# Sheet1_v3.net
KiCad netlist of a schematic drawn in Altium Designer
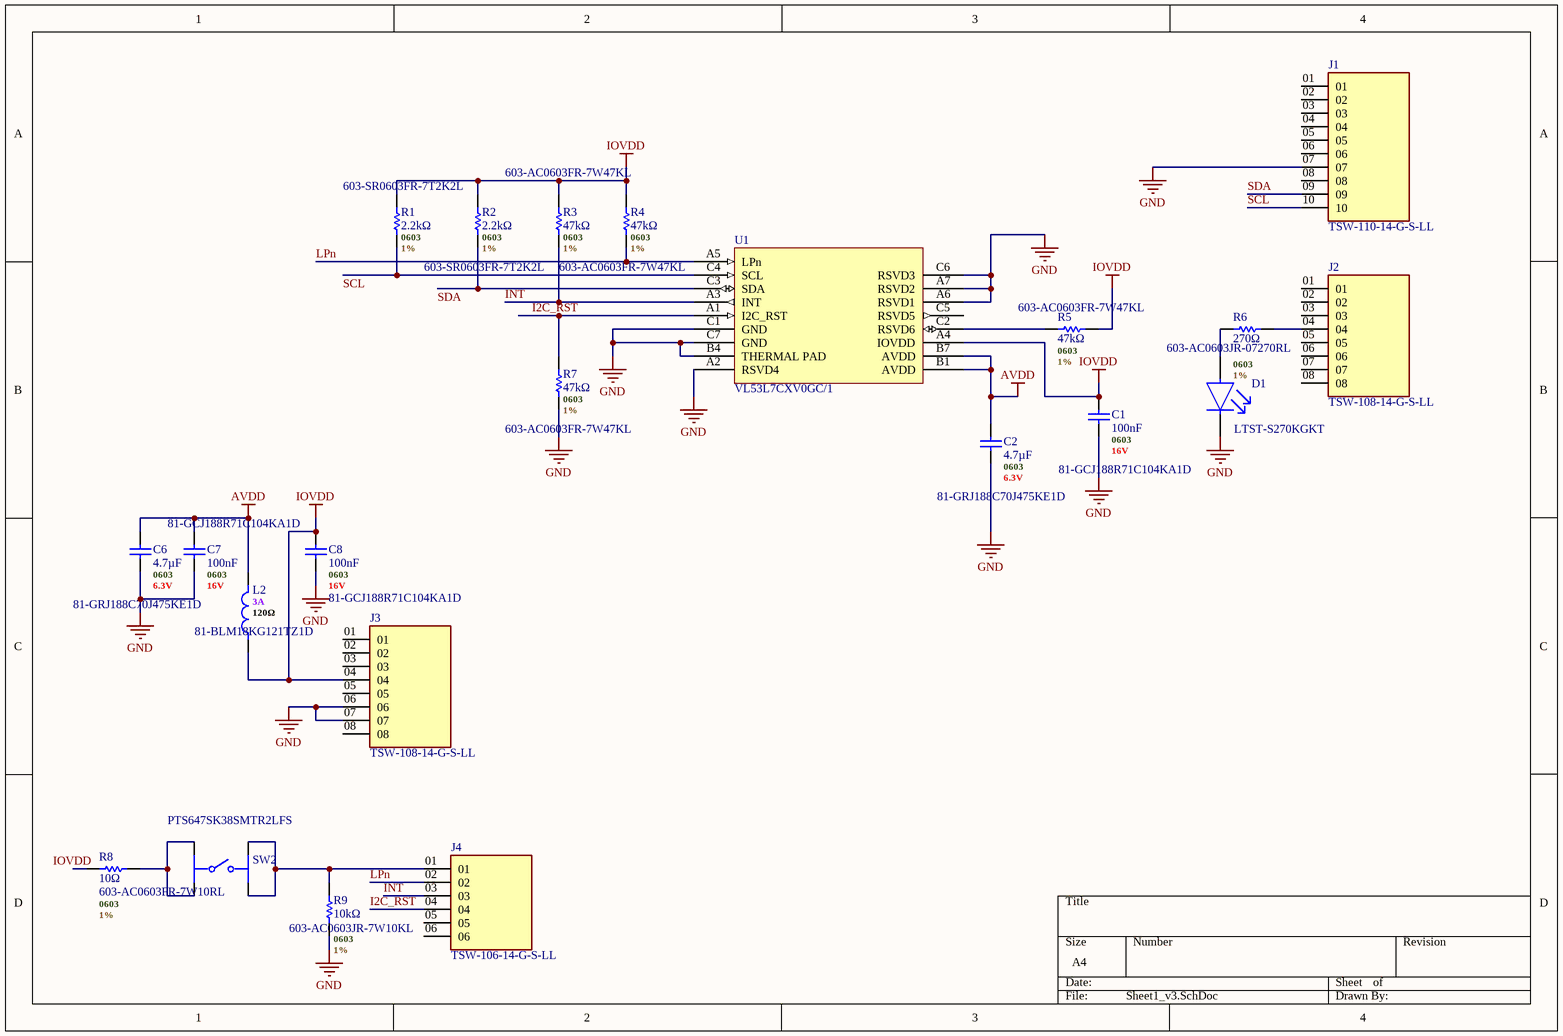
[diagram p0: Sheet1_v3.SchDoc]

(export (version "E")
  (design (tool "Eeschema 10.0.6"))
  (components
    (comp (ref "C1")
      (value "100nF")
      (footprint "C0603 - MURATA")
      (description "Ceramic Capacitor, Ceramic, 16V, 10% +Tol, 10% -Tol, X7R, 15% TC, 0.1uF, Surface Mount, 0603")
      (fields
        (field (name "MANUFACTURER") "Murata")
        (field (name "MANUFACTURER PART NUMBER") "GCJ188R71C104KA01D")
        (field (name ".CASE/PACKAGE") "0603")
        (field (name ".VOLTAGE RATING (DC)") "16V")
        (field (name "SUPPLIER PART NUMBER 1") "81-GCJ188R71C104KA1D")
      )
      (libsource (lib "CAP_GCJ188R71C104KA01D") (part "CAP - GENERIC"))
    )
    (comp (ref "C2")
      (value "4.7µF")
      (footprint "C0603 - MURATA")
      (description "GRJ Series 0603 6.3 V 4.7 uF ±10% X7S SMT Multilayer Ceramic Capacitor")
      (fields
        (field (name "MANUFACTURER") "Murata")
        (field (name "MANUFACTURER PART NUMBER") "GRJ188C70J475KE11D")
        (field (name ".CASE/PACKAGE") "0603")
        (field (name ".VOLTAGE RATING (DC)") "6.3V")
        (field (name "SUPPLIER PART NUMBER 1") "81-GRJ188C70J475KE1D")
      )
      (libsource (lib "CAP_GRJ188C70J475KE11D") (part "CAP - GENERIC"))
    )
    (comp (ref "C6")
      (value "4.7µF")
      (footprint "C0603 - MURATA")
      (description "GRJ Series 0603 6.3 V 4.7 uF ±10% X7S SMT Multilayer Ceramic Capacitor")
      (fields
        (field (name "MANUFACTURER") "Murata")
        (field (name "MANUFACTURER PART NUMBER") "GRJ188C70J475KE11D")
        (field (name ".CASE/PACKAGE") "0603")
        (field (name ".VOLTAGE RATING (DC)") "6.3V")
        (field (name "SUPPLIER PART NUMBER 1") "81-GRJ188C70J475KE1D")
      )
      (libsource (lib "CAP_GRJ188C70J475KE11D") (part "CAP - GENERIC"))
    )
    (comp (ref "C7")
      (value "100nF")
      (footprint "C0603 - MURATA")
      (description "Ceramic Capacitor, Ceramic, 16V, 10% +Tol, 10% -Tol, X7R, 15% TC, 0.1uF, Surface Mount, 0603")
      (fields
        (field (name "MANUFACTURER") "Murata")
        (field (name "MANUFACTURER PART NUMBER") "GCJ188R71C104KA01D")
        (field (name ".CASE/PACKAGE") "0603")
        (field (name ".VOLTAGE RATING (DC)") "16V")
        (field (name "SUPPLIER PART NUMBER 1") "81-GCJ188R71C104KA1D")
      )
      (libsource (lib "CAP_GCJ188R71C104KA01D") (part "CAP - GENERIC"))
    )
    (comp (ref "C8")
      (value "100nF")
      (footprint "C0603 - MURATA")
      (description "Ceramic Capacitor, Ceramic, 16V, 10% +Tol, 10% -Tol, X7R, 15% TC, 0.1uF, Surface Mount, 0603")
      (fields
        (field (name "MANUFACTURER") "Murata")
        (field (name "MANUFACTURER PART NUMBER") "GCJ188R71C104KA01D")
        (field (name ".CASE/PACKAGE") "0603")
        (field (name ".VOLTAGE RATING (DC)") "16V")
        (field (name "SUPPLIER PART NUMBER 1") "81-GCJ188R71C104KA1D")
      )
      (libsource (lib "CAP_GCJ188R71C104KA01D") (part "CAP - GENERIC"))
    )
    (comp (ref "D1")
      (value "LTST-S270KGKT")
      (footprint "FP-LTST-S270KGKT-MFG")
      (description "LED GREEN CLEAR CHIP SMD R/A")
      (libsource (lib "Altium Content Vault") (part "8706943c75ba83719d021d2fdc84c58"))
    )
    (comp (ref "J1")
      (value "TSW-110-14-G-S-LL")
      (footprint "SAMTEC_TSW-110-14-G-S-LL")
      (libsource (lib "TSW-110-14-G-S-LL") (part "TSW-110-14-G-S-LL"))
    )
    (comp (ref "J2")
      (value "TSW-108-14-G-S-LL")
      (footprint "SAMTEC_TSW-108-14-G-S-LL")
      (libsource (lib "TSW-108-14-G-S-LL") (part "TSW-108-14-G-S-LL"))
    )
    (comp (ref "J3")
      (value "TSW-108-14-G-S-LL")
      (footprint "SAMTEC_TSW-108-14-G-S-LL")
      (libsource (lib "TSW-108-14-G-S-LL") (part "TSW-108-14-G-S-LL"))
    )
    (comp (ref "J4")
      (value "TSW-106-14-G-S-LL")
      (footprint "SAMTEC_TSW-106-14-G-S-LL")
      (libsource (lib "TSW-106-14-G-S-LL") (part "TSW-106-14-G-S-LL"))
    )
    (comp (ref "L2")
      (value "BLM18KG121TZ1D")
      (footprint "BLM18KG121TZ1D")
      (description "Ferrite Beads Multi-Layer Power 120Ohm 25% 100MHz 3A 0.03Ohm DCR 0603 T/R Automotive AEC-Q200")
      (fields
        (field (name "MANUFACTURER") "Murata")
        (field (name "TOLERANCE") "25%")
        (field (name ".RMS CURRENT (IRMS)") "3A")
        (field (name ".VALUE") "120Ω")
        (field (name "SUPPLIER PART NUMBER 1") "81-BLM18KG121TZ1D")
      )
      (libsource (lib "INDUCTOR_BLM18KG121TZ1D") (part "INDUCTOR_BLM18KG121TZ1D"))
    )
    (comp (ref "R1")
      (value "2.2kΩ")
      (footprint "R0603 - YAGEO")
      (description "Surge Chip Resistor Automotive Grade Thick Film 0603 2.2kOhm 1% Paper T/R")
      (fields
        (field (name "MANUFACTURER") "Yageo Group")
        (field (name "MANUFACTURER PART NUMBER") "SR0603FR-7T2K2L")
        (field (name ".CASE/PACKAGE") "0603")
        (field (name ".TOLERANCE") "1%")
        (field (name "SUPPLIER PART NUMBER 1") "603-SR0603FR-7T2K2L")
      )
      (libsource (lib "RESISTOR - GENERIC") (part "RESISTOR - GENERIC"))
    )
    (comp (ref "R2")
      (value "2.2kΩ")
      (footprint "R0603 - YAGEO")
      (description "Surge Chip Resistor Automotive Grade Thick Film 0603 2.2kOhm 1% Paper T/R")
      (fields
        (field (name "MANUFACTURER") "Yageo Group")
        (field (name "MANUFACTURER PART NUMBER") "SR0603FR-7T2K2L")
        (field (name ".CASE/PACKAGE") "0603")
        (field (name ".TOLERANCE") "1%")
        (field (name "SUPPLIER PART NUMBER 1") "603-SR0603FR-7T2K2L")
      )
      (libsource (lib "RESISTOR - GENERIC") (part "RESISTOR - GENERIC"))
    )
    (comp (ref "R3")
      (value "47kΩ")
      (footprint "R0603 - YAGEO")
      (fields
        (field (name "MANUFACTURER") "Yageo Group")
        (field (name "MANUFACTURER PART NUMBER") "AC0603FR-7W47KL")
        (field (name "TOLERANCE") "1%")
        (field (name ".CASE/PACKAGE") "0603")
        (field (name ".TOLERANCE") "1%")
        (field (name "SUPPLIER PART NUMBER 1") "603-AC0603FR-7W47KL")
      )
      (libsource (lib "RESISTOR_AC0603FR-7W47KLSchLib") (part "RESISTOR - GENERIC"))
    )
    (comp (ref "R4")
      (value "47kΩ")
      (footprint "R0603 - YAGEO")
      (fields
        (field (name "MANUFACTURER") "Yageo Group")
        (field (name "MANUFACTURER PART NUMBER") "AC0603FR-7W47KL")
        (field (name "TOLERANCE") "1%")
        (field (name ".CASE/PACKAGE") "0603")
        (field (name ".TOLERANCE") "1%")
        (field (name "SUPPLIER PART NUMBER 1") "603-AC0603FR-7W47KL")
      )
      (libsource (lib "RESISTOR_AC0603FR-7W47KLSchLib") (part "RESISTOR - GENERIC"))
    )
    (comp (ref "R5")
      (value "47kΩ")
      (footprint "R0603 - YAGEO")
      (fields
        (field (name "MANUFACTURER") "Yageo Group")
        (field (name "MANUFACTURER PART NUMBER") "AC0603FR-7W47KL")
        (field (name "TOLERANCE") "1%")
        (field (name ".CASE/PACKAGE") "0603")
        (field (name ".TOLERANCE") "1%")
        (field (name "SUPPLIER PART NUMBER 1") "603-AC0603FR-7W47KL")
      )
      (libsource (lib "RESISTOR_AC0603FR-7W47KLSchLib") (part "RESISTOR - GENERIC"))
    )
    (comp (ref "R6")
      (value "270Ω")
      (footprint "R0603 - YAGEO")
      (description "Res Thick Film 0603 270 Ohm 5% 0.1W(1/10W) ±100ppm/C Pad SMD Automotive T/R")
      (fields
        (field (name "MANUFACTURER") "Yageo Group")
        (field (name "TOLERANCE") "1%")
        (field (name "SUPPLIER PART NUMBER") "603-AC0603JR-07270RL")
        (field (name ".CASE/PACKAGE") "0603")
        (field (name ".TOLERANCE") "1%")
      )
      (libsource (lib "RESISTOR_AC0603JR-07270RL") (part "RESISTOR - GENERIC"))
    )
    (comp (ref "R7")
      (value "47kΩ")
      (footprint "R0603 - YAGEO")
      (fields
        (field (name "MANUFACTURER") "Yageo Group")
        (field (name "MANUFACTURER PART NUMBER") "AC0603FR-7W47KL")
        (field (name "TOLERANCE") "1%")
        (field (name ".CASE/PACKAGE") "0603")
        (field (name ".TOLERANCE") "1%")
        (field (name "SUPPLIER PART NUMBER 1") "603-AC0603FR-7W47KL")
      )
      (libsource (lib "RESISTOR_AC0603FR-7W47KLSchLib") (part "RESISTOR - GENERIC"))
    )
    (comp (ref "R8")
      (value "10Ω")
      (footprint "R0603 - YAGEO")
      (fields
        (field (name "MANUFACTURER") "Yageo Group")
        (field (name "TOLERANCE") "1%")
        (field (name "MANUFACTURER PART NUMBER") "AC0603JR-7W68RL")
        (field (name "SUPPLIER PART NUMBER") "603-AC0603FR-7W10RL")
        (field (name ".CASE/PACKAGE") "0603")
        (field (name ".TOLERANCE") "1%")
      )
      (libsource (lib "RESISTOR_AC0603FR-7W10RL") (part "RESISTOR - GENERIC"))
    )
    (comp (ref "R9")
      (value "10kΩ")
      (footprint "R0603 - YAGEO")
      (fields
        (field (name "MANUFACTURER") "Yageo Group")
        (field (name "TOLERANCE") "1%")
        (field (name "MANUFACTURER PART NUMBER") "AC0603JR-7W68RL")
        (field (name "SUPPLIER PART NUMBER") "603-AC0603JR-7W10KL")
        (field (name ".CASE/PACKAGE") "0603")
        (field (name ".TOLERANCE") "1%")
      )
      (libsource (lib "RESISTOR_AC0603JR-7W10KL") (part "RESISTOR - GENERIC"))
    )
    (comp (ref "SW2")
      (value "PTS647SK38SMTR2LFS")
      (footprint "FP-PTS647SK38SMTR2LFS-MFG")
      (description "TACT 4.5 X 4.5, 3.8 MM H, 2.5N,")
      (libsource (lib "Altium Content Vault") (part "1adf0dd01260c80cf25a44bfd6b99ba"))
    )
    (comp (ref "U1")
      (value "VL53L7CXV0GC/1")
      (footprint "VL53L7CXV0GC1")
      (description "Proximity Sensor Time of Flight(TOF) 350cm 2.5V to 3.3V/3V to 3.6VDC 16-Pin OPT LGA EP T/R")
      (fields
        (field (name "MANUFACTURER") "STMicroelectronics")
        (field (name "MANUFACTURER PART NUMBER") "VL53L8CXV0GC/1")
      )
      (libsource (lib "VL53L7CXV0GC-1") (part "VL53L7CXV0GC/1"))
    )
  )
  (nets
    (net (code "1") (name "/I2C_RST") (class "Default")
      (node (ref "J4") (pin "04") (pinfunction "04_04") (pintype "passive"))
      (node (ref "R7") (pin "2") (pinfunction "2_2") (pintype "passive"))
      (node (ref "U1") (pin "A1") (pinfunction "I2C_RST_A1") (pintype "input"))
    )
    (net (code "2") (name "/INT") (class "Default")
      (node (ref "J4") (pin "03") (pinfunction "03_03") (pintype "passive"))
      (node (ref "R3") (pin "1") (pinfunction "1_1") (pintype "passive"))
      (node (ref "U1") (pin "A3") (pinfunction "INT_A3") (pintype "output"))
    )
    (net (code "3") (name "/LPn") (class "Default")
      (node (ref "J4") (pin "02") (pinfunction "02_02") (pintype "passive"))
      (node (ref "R4") (pin "1") (pinfunction "1_1") (pintype "passive"))
      (node (ref "U1") (pin "A5") (pinfunction "LPn_A5") (pintype "input"))
    )
    (net (code "4") (name "/SCL") (class "Default")
      (node (ref "J1") (pin "10") (pinfunction "10_10") (pintype "passive"))
      (node (ref "R1") (pin "1") (pinfunction "1_1") (pintype "passive"))
      (node (ref "U1") (pin "C4") (pinfunction "SCL_C4") (pintype "input"))
    )
    (net (code "5") (name "/SDA") (class "Default")
      (node (ref "J1") (pin "09") (pinfunction "09_09") (pintype "passive"))
      (node (ref "R2") (pin "1") (pinfunction "1_1") (pintype "passive"))
      (node (ref "U1") (pin "C3") (pinfunction "SDA_C3") (pintype "bidirectional"))
    )
    (net (code "6") (name "AVDD") (class "Default")
      (node (ref "C2") (pin "2") (pinfunction "2_2") (pintype "passive"))
      (node (ref "C6") (pin "2") (pinfunction "2_2") (pintype "passive"))
      (node (ref "C7") (pin "2") (pinfunction "2_2") (pintype "passive"))
      (node (ref "L2") (pin "2") (pinfunction "2_2") (pintype "passive"))
      (node (ref "U1") (pin "B1") (pinfunction "AVDD_B1") (pintype "power_in"))
      (node (ref "U1") (pin "B7") (pinfunction "AVDD_B7") (pintype "power_in"))
    )
    (net (code "7") (name "GND") (class "Default")
      (node (ref "C1") (pin "1") (pinfunction "1_1") (pintype "passive"))
      (node (ref "C2") (pin "1") (pinfunction "1_1") (pintype "passive"))
      (node (ref "C6") (pin "1") (pinfunction "1_1") (pintype "passive"))
      (node (ref "C7") (pin "1") (pinfunction "1_1") (pintype "passive"))
      (node (ref "C8") (pin "1") (pinfunction "1_1") (pintype "passive"))
      (node (ref "D1") (pin "1") (pinfunction "C_1") (pintype "passive"))
      (node (ref "J1") (pin "07") (pinfunction "07_07") (pintype "passive"))
      (node (ref "J3") (pin "06") (pinfunction "06_06") (pintype "passive"))
      (node (ref "J3") (pin "07") (pinfunction "07_07") (pintype "passive"))
      (node (ref "R7") (pin "1") (pinfunction "1_1") (pintype "passive"))
      (node (ref "R9") (pin "1") (pinfunction "1_1") (pintype "passive"))
      (node (ref "U1") (pin "A2") (pinfunction "RSVD4_A2") (pintype "passive"))
      (node (ref "U1") (pin "A6") (pinfunction "RSVD1_A6") (pintype "passive"))
      (node (ref "U1") (pin "A7") (pinfunction "RSVD2_A7") (pintype "passive"))
      (node (ref "U1") (pin "B4") (pinfunction "THERMAL_PAD_B4") (pintype "passive"))
      (node (ref "U1") (pin "C1") (pinfunction "GND_C1") (pintype "power_in"))
      (node (ref "U1") (pin "C6") (pinfunction "RSVD3_C6") (pintype "passive"))
      (node (ref "U1") (pin "C7") (pinfunction "GND_C7") (pintype "power_in"))
    )
    (net (code "8") (name "IOVDD") (class "Default")
      (node (ref "C1") (pin "2") (pinfunction "2_2") (pintype "passive"))
      (node (ref "C8") (pin "2") (pinfunction "2_2") (pintype "passive"))
      (node (ref "J3") (pin "04") (pinfunction "04_04") (pintype "passive"))
      (node (ref "L2") (pin "1") (pinfunction "1_1") (pintype "passive"))
      (node (ref "R1") (pin "2") (pinfunction "2_2") (pintype "passive"))
      (node (ref "R2") (pin "2") (pinfunction "2_2") (pintype "passive"))
      (node (ref "R3") (pin "2") (pinfunction "2_2") (pintype "passive"))
      (node (ref "R4") (pin "2") (pinfunction "2_2") (pintype "passive"))
      (node (ref "R5") (pin "2") (pinfunction "2_2") (pintype "passive"))
      (node (ref "R8") (pin "1") (pinfunction "1_1") (pintype "passive"))
      (node (ref "U1") (pin "A4") (pinfunction "IOVDD_A4") (pintype "power_in"))
    )
    (net (code "9") (name "Net-(D1-A)") (class "Default")
      (node (ref "D1") (pin "2") (pinfunction "A_2") (pintype "passive"))
      (node (ref "R6") (pin "1") (pinfunction "1_1") (pintype "passive"))
    )
    (net (code "10") (name "Net-(J2-Pad04)") (class "Default")
      (node (ref "J2") (pin "04") (pinfunction "04_04") (pintype "passive"))
      (node (ref "R6") (pin "2") (pinfunction "2_2") (pintype "passive"))
    )
    (net (code "11") (name "Net-(J4-Pad01)") (class "Default")
      (node (ref "J4") (pin "01") (pinfunction "01_01") (pintype "passive"))
      (node (ref "R9") (pin "2") (pinfunction "2_2") (pintype "passive"))
      (node (ref "SW2") (pin "1") (pinfunction "1_1") (pintype "passive"))
      (node (ref "SW2") (pin "2") (pinfunction "2_2") (pintype "passive"))
    )
    (net (code "12") (name "Net-(R8-Pad2)") (class "Default")
      (node (ref "R8") (pin "2") (pinfunction "2_2") (pintype "passive"))
      (node (ref "SW2") (pin "3") (pinfunction "3_3") (pintype "passive"))
      (node (ref "SW2") (pin "4") (pinfunction "4_4") (pintype "passive"))
    )
    (net (code "13") (name "Net-(U1-RSVD6)") (class "Default")
      (node (ref "R5") (pin "1") (pinfunction "1_1") (pintype "passive"))
      (node (ref "U1") (pin "C2") (pinfunction "RSVD6_C2") (pintype "bidirectional"))
    )
    (net (code "14") (name "unconnected-(J1-Pad01)") (class "Default")
      (node (ref "J1") (pin "01") (pinfunction "01_01") (pintype "passive"))
    )
    (net (code "15") (name "unconnected-(J1-Pad02)") (class "Default")
      (node (ref "J1") (pin "02") (pinfunction "02_02") (pintype "passive"))
    )
    (net (code "16") (name "unconnected-(J1-Pad03)") (class "Default")
      (node (ref "J1") (pin "03") (pinfunction "03_03") (pintype "passive"))
    )
    (net (code "17") (name "unconnected-(J1-Pad04)") (class "Default")
      (node (ref "J1") (pin "04") (pinfunction "04_04") (pintype "passive"))
    )
    (net (code "18") (name "unconnected-(J1-Pad05)") (class "Default")
      (node (ref "J1") (pin "05") (pinfunction "05_05") (pintype "passive"))
    )
    (net (code "19") (name "unconnected-(J1-Pad06)") (class "Default")
      (node (ref "J1") (pin "06") (pinfunction "06_06") (pintype "passive"))
    )
    (net (code "20") (name "unconnected-(J1-Pad08)") (class "Default")
      (node (ref "J1") (pin "08") (pinfunction "08_08") (pintype "passive"))
    )
    (net (code "21") (name "unconnected-(J2-Pad01)") (class "Default")
      (node (ref "J2") (pin "01") (pinfunction "01_01") (pintype "passive"))
    )
    (net (code "22") (name "unconnected-(J2-Pad02)") (class "Default")
      (node (ref "J2") (pin "02") (pinfunction "02_02") (pintype "passive"))
    )
    (net (code "23") (name "unconnected-(J2-Pad03)") (class "Default")
      (node (ref "J2") (pin "03") (pinfunction "03_03") (pintype "passive"))
    )
    (net (code "24") (name "unconnected-(J2-Pad05)") (class "Default")
      (node (ref "J2") (pin "05") (pinfunction "05_05") (pintype "passive"))
    )
    (net (code "25") (name "unconnected-(J2-Pad06)") (class "Default")
      (node (ref "J2") (pin "06") (pinfunction "06_06") (pintype "passive"))
    )
    (net (code "26") (name "unconnected-(J2-Pad07)") (class "Default")
      (node (ref "J2") (pin "07") (pinfunction "07_07") (pintype "passive"))
    )
    (net (code "27") (name "unconnected-(J2-Pad08)") (class "Default")
      (node (ref "J2") (pin "08") (pinfunction "08_08") (pintype "passive"))
    )
    (net (code "28") (name "unconnected-(J3-Pad01)") (class "Default")
      (node (ref "J3") (pin "01") (pinfunction "01_01") (pintype "passive"))
    )
    (net (code "29") (name "unconnected-(J3-Pad02)") (class "Default")
      (node (ref "J3") (pin "02") (pinfunction "02_02") (pintype "passive"))
    )
    (net (code "30") (name "unconnected-(J3-Pad03)") (class "Default")
      (node (ref "J3") (pin "03") (pinfunction "03_03") (pintype "passive"))
    )
    (net (code "31") (name "unconnected-(J3-Pad05)") (class "Default")
      (node (ref "J3") (pin "05") (pinfunction "05_05") (pintype "passive"))
    )
    (net (code "32") (name "unconnected-(J3-Pad08)") (class "Default")
      (node (ref "J3") (pin "08") (pinfunction "08_08") (pintype "passive"))
    )
    (net (code "33") (name "unconnected-(J4-Pad05)") (class "Default")
      (node (ref "J4") (pin "05") (pinfunction "05_05") (pintype "passive"))
    )
    (net (code "34") (name "unconnected-(J4-Pad06)") (class "Default")
      (node (ref "J4") (pin "06") (pinfunction "06_06") (pintype "passive"))
    )
    (net (code "35") (name "unconnected-(U1-RSVD5-PadC5)") (class "Default")
      (node (ref "U1") (pin "C5") (pinfunction "RSVD5_C5") (pintype "output"))
    )
  )
)
